# EVB-NORA-B2_SCHEM_0007_mikroE.net
KiCad netlist of a schematic drawn in Altium Designer
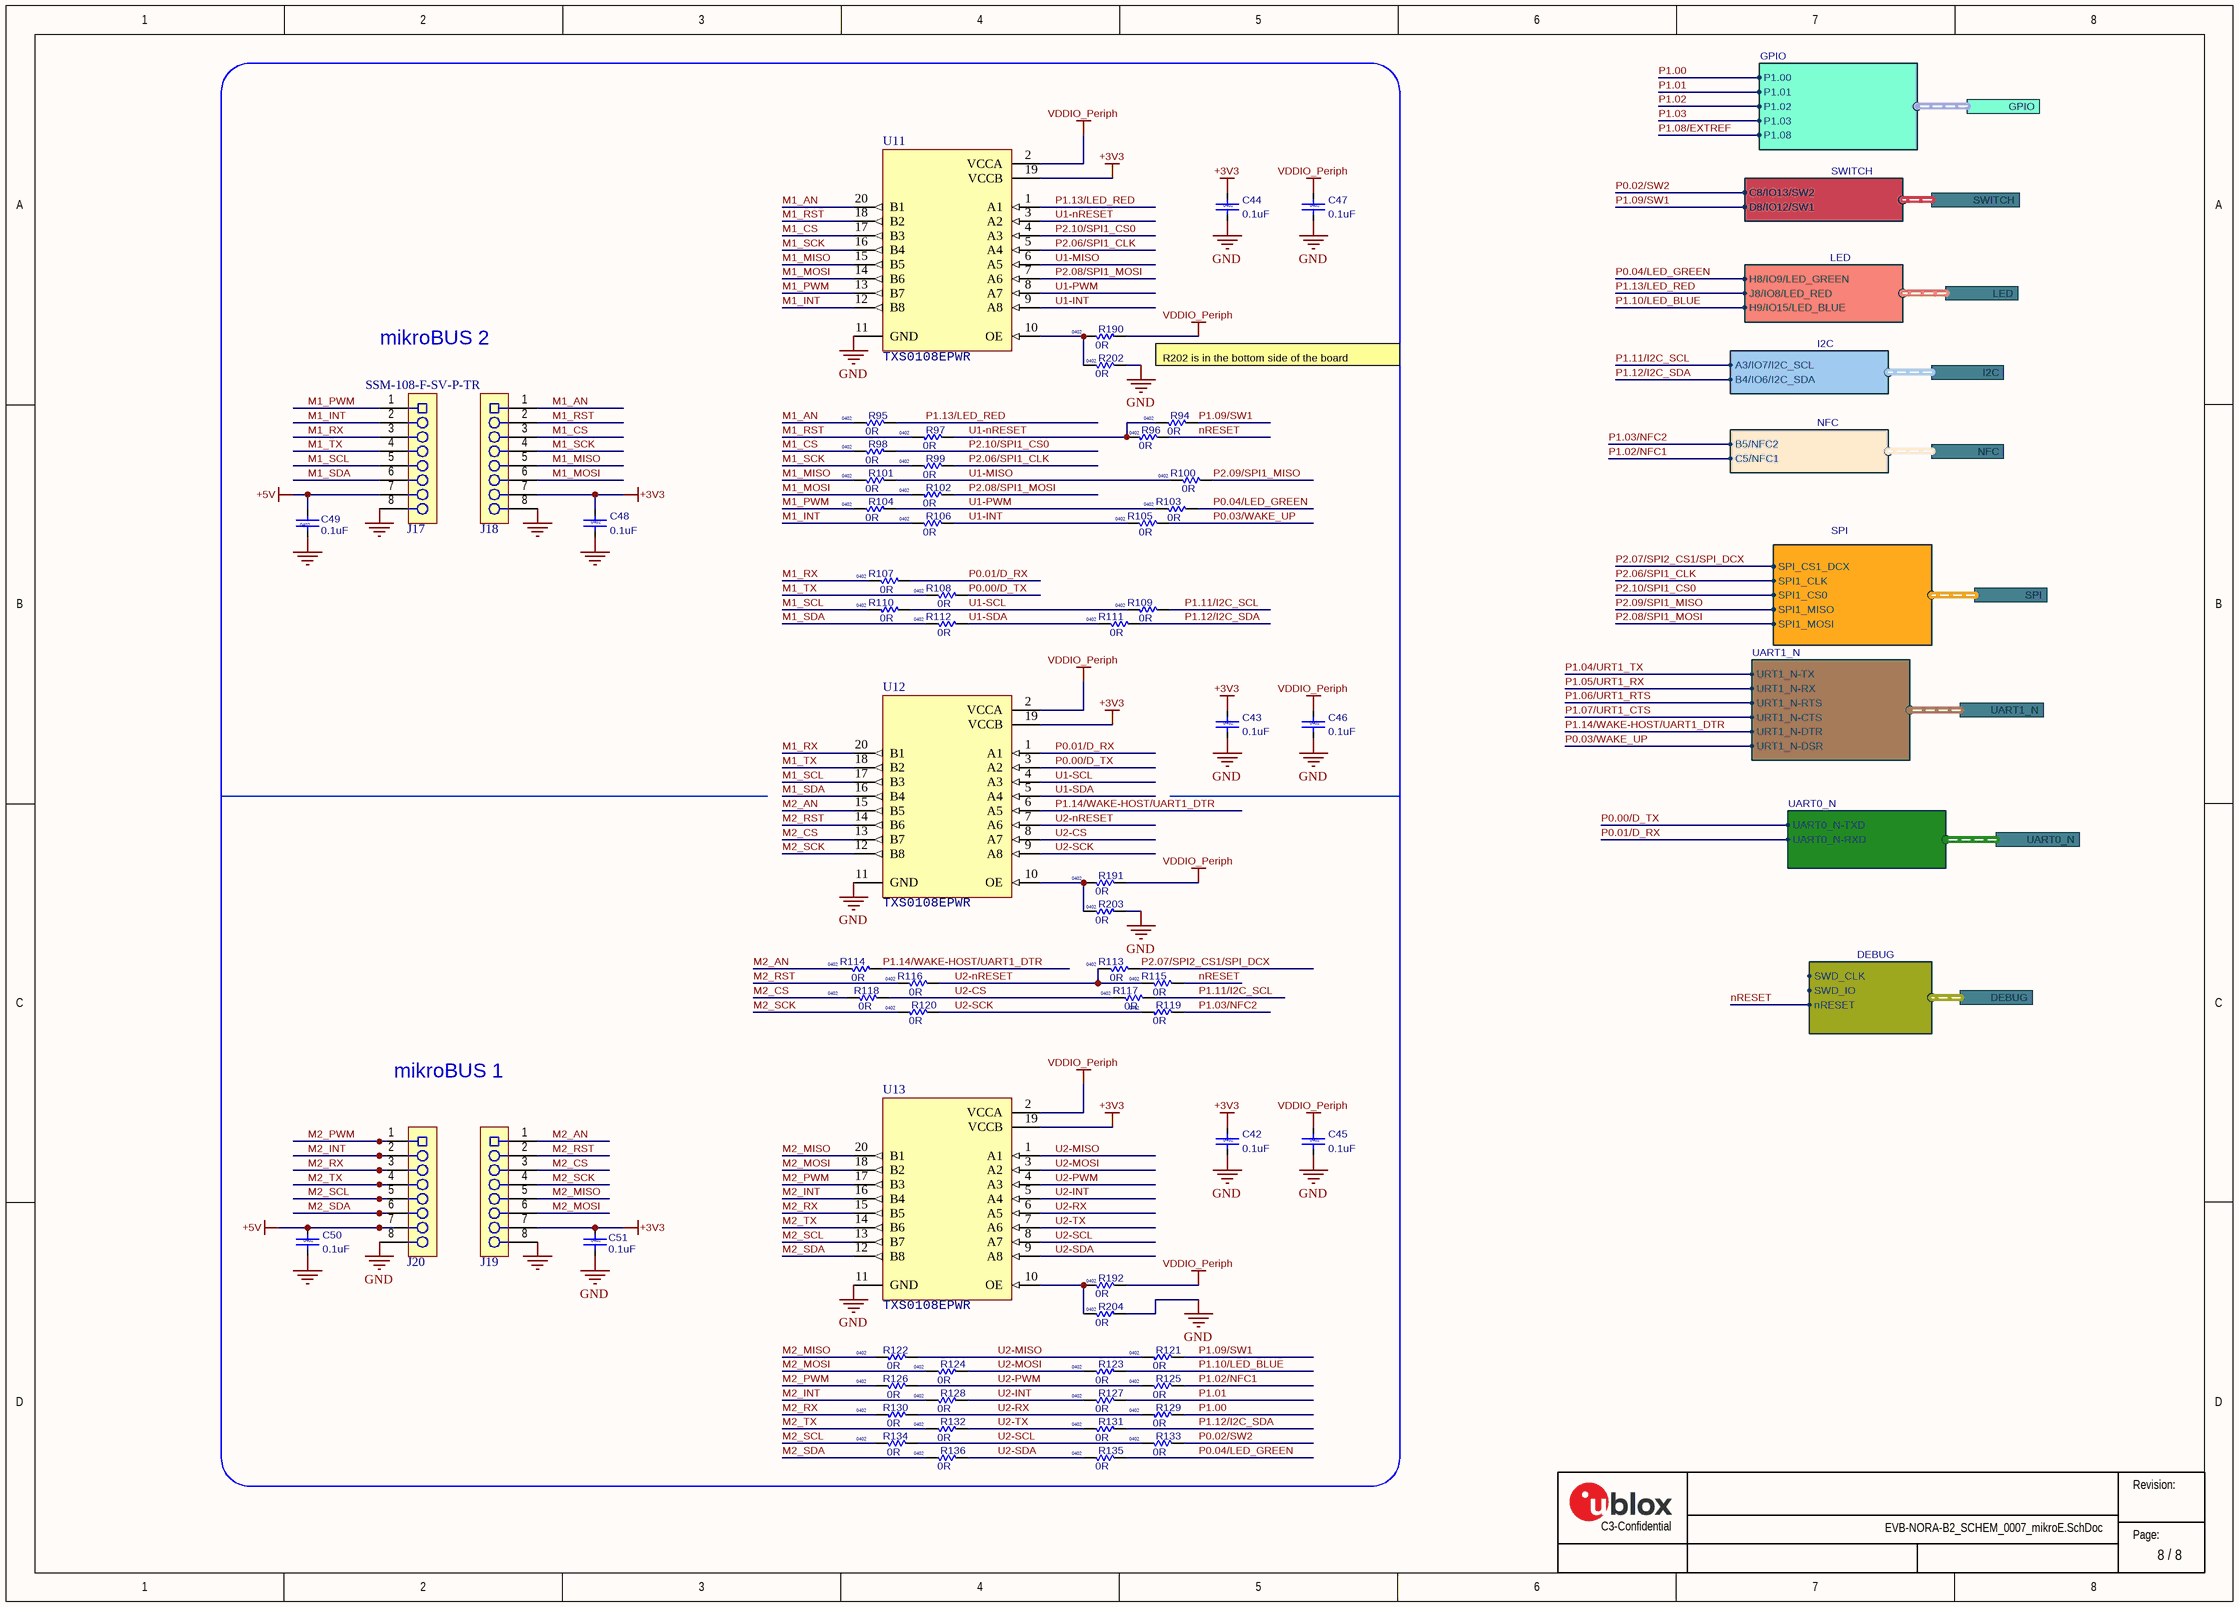
[diagram p0: EVB-NORA-B2_SCHEM_0007_mikroE.SchDoc]

(export (version "E")
  (design (tool "Eeschema 10.0.6"))
  (components
    (comp (ref "C42")
      (value "0.1uF")
      (footprint "Cap 0402 HD")
      (description "Cap, Ceramic 0.1uF 10V 10% X5R 0402")
      (fields
        (field (name "SIZE") "0402")
        (field (name "PART NUMBER") "120-00016")
        (field (name "MANUFACTURER") "Murata Electronics North America")
      )
      (libsource (lib "Arena_Parts_DB_Lib") (part "Cap Chip"))
    )
    (comp (ref "C43")
      (value "0.1uF")
      (footprint "Cap 0402 HD")
      (description "Cap, Ceramic 0.1uF 10V 10% X5R 0402")
      (fields
        (field (name "SIZE") "0402")
        (field (name "PART NUMBER") "120-00016")
        (field (name "MANUFACTURER") "Murata Electronics North America")
      )
      (libsource (lib "Arena_Parts_DB_Lib") (part "Cap Chip"))
    )
    (comp (ref "C44")
      (value "0.1uF")
      (footprint "Cap 0402 HD")
      (description "Cap, Ceramic 0.1uF 10V 10% X5R 0402")
      (fields
        (field (name "SIZE") "0402")
        (field (name "PART NUMBER") "120-00016")
        (field (name "MANUFACTURER") "Murata Electronics North America")
      )
      (libsource (lib "Arena_Parts_DB_Lib") (part "Cap Chip"))
    )
    (comp (ref "C45")
      (value "0.1uF")
      (footprint "Cap 0402 HD")
      (description "Cap, Ceramic 0.1uF 10V 10% X5R 0402")
      (fields
        (field (name "SIZE") "0402")
        (field (name "PART NUMBER") "120-00016")
        (field (name "MANUFACTURER") "Murata Electronics North America")
      )
      (libsource (lib "Arena_Parts_DB_Lib") (part "Cap Chip"))
    )
    (comp (ref "C46")
      (value "0.1uF")
      (footprint "Cap 0402 HD")
      (description "Cap, Ceramic 0.1uF 10V 10% X5R 0402")
      (fields
        (field (name "SIZE") "0402")
        (field (name "PART NUMBER") "120-00016")
        (field (name "MANUFACTURER") "Murata Electronics North America")
      )
      (libsource (lib "Arena_Parts_DB_Lib") (part "Cap Chip"))
    )
    (comp (ref "C47")
      (value "0.1uF")
      (footprint "Cap 0402 HD")
      (description "Cap, Ceramic 0.1uF 10V 10% X5R 0402")
      (fields
        (field (name "SIZE") "0402")
        (field (name "PART NUMBER") "120-00016")
        (field (name "MANUFACTURER") "Murata Electronics North America")
      )
      (libsource (lib "Arena_Parts_DB_Lib") (part "Cap Chip"))
    )
    (comp (ref "C48")
      (value "0.1uF")
      (footprint "Cap 0402 HD")
      (description "Cap, Ceramic 0.1uF 10V 10% X5R 0402")
      (fields
        (field (name "SIZE") "0402")
        (field (name "PART NUMBER") "120-00016")
        (field (name "MANUFACTURER") "Murata Electronics North America")
      )
      (libsource (lib "Arena_Parts_DB_Lib") (part "Cap Chip"))
    )
    (comp (ref "C49")
      (value "0.1uF")
      (footprint "Cap 0402 HD")
      (description "Cap, Ceramic 0.1uF 10V 10% X5R 0402")
      (fields
        (field (name "SIZE") "0402")
        (field (name "PART NUMBER") "120-00016")
        (field (name "MANUFACTURER") "Murata Electronics North America")
      )
      (libsource (lib "Arena_Parts_DB_Lib") (part "Cap Chip"))
    )
    (comp (ref "C50")
      (value "0.1uF")
      (footprint "Cap 0402 HD")
      (description "Cap, Ceramic 0.1uF 10V 10% X5R 0402")
      (fields
        (field (name "SIZE") "0402")
        (field (name "PART NUMBER") "120-00016")
        (field (name "MANUFACTURER") "Murata Electronics North America")
      )
      (libsource (lib "Arena_Parts_DB_Lib") (part "Cap Chip"))
    )
    (comp (ref "C51")
      (value "0.1uF")
      (footprint "Cap 0402 HD")
      (description "Cap, Ceramic 0.1uF 10V 10% X5R 0402")
      (fields
        (field (name "SIZE") "0402")
        (field (name "PART NUMBER") "120-00016")
        (field (name "MANUFACTURER") "Murata Electronics North America")
      )
      (libsource (lib "Arena_Parts_DB_Lib") (part "Cap Chip"))
    )
    (comp (ref "J17")
      (value "130-00102")
      (footprint "SKT-0.1P-SSM-108-L-SV")
      (description "Socket Strip 0.1\" 8 Pin 1Row SMD Black")
      (fields
        (field (name "MANUFACTURER PART NUMBER 1") "SSM-108-F-SV-P-TR")
        (field (name "VOLTAGE") "572VDC")
      )
      (libsource (lib "Arena_Parts_DB_Lib") (part "CON-8Pin_1Row"))
    )
    (comp (ref "J18")
      (value "130-00102")
      (footprint "SKT-0.1P-SSM-108-L-SV")
      (description "Socket Strip 0.1\" 8 Pin 1Row SMD Black")
      (fields (field (name "VOLTAGE") "572VDC"))
      (libsource (lib "") (part "CON-8Pin_1Row_1"))
    )
    (comp (ref "J19")
      (value "130-00102")
      (footprint "SKT-0.1P-SSM-108-L-SV")
      (description "Socket Strip 0.1\" 8 Pin 1Row SMD Black")
      (fields (field (name "VOLTAGE") "572VDC"))
      (libsource (lib "") (part "CON-8Pin_1Row_1"))
    )
    (comp (ref "J20")
      (value "130-00102")
      (footprint "SKT-0.1P-SSM-108-L-SV")
      (description "Socket Strip 0.1\" 8 Pin 1Row SMD Black")
      (fields (field (name "VOLTAGE") "572VDC"))
      (libsource (lib "Arena_Parts_DB_Lib") (part "CON-8Pin_1Row"))
    )
    (comp (ref "R94")
      (value "0R")
      (footprint "RES 0402 HD")
      (description "RES THICK FILM CHIP 0402 0R 0 100mW")
      (fields
        (field (name "SIZE") "0402")
        (field (name "PART NUMBER") "UBXH18-0003002")
        (field (name "TOLERANCE") "0")
        (field (name "EDITOR") "charlotte.biber")
        (field (name "RELEASED BY") "peter.mueller")
      )
      (libsource (lib "UBX_Parts_DB_Lib") (part "Res sm"))
    )
    (comp (ref "R95")
      (value "0R")
      (footprint "RES 0402 HD")
      (description "RES THICK FILM CHIP 0402 0R 0 100mW")
      (fields
        (field (name "SIZE") "0402")
        (field (name "PART NUMBER") "UBXH18-0003002")
        (field (name "TOLERANCE") "0")
        (field (name "EDITOR") "charlotte.biber")
        (field (name "RELEASED BY") "peter.mueller")
      )
      (libsource (lib "UBX_Parts_DB_Lib") (part "Res sm"))
    )
    (comp (ref "R96")
      (value "0R")
      (footprint "RES 0402 HD")
      (description "RES THICK FILM CHIP 0402 0R 0 100mW")
      (fields
        (field (name "SIZE") "0402")
        (field (name "PART NUMBER") "UBXH18-0003002")
        (field (name "TOLERANCE") "0")
        (field (name "EDITOR") "charlotte.biber")
        (field (name "RELEASED BY") "peter.mueller")
      )
      (libsource (lib "UBX_Parts_DB_Lib") (part "Res sm"))
    )
    (comp (ref "R97")
      (value "0R")
      (footprint "RES 0402 HD")
      (description "RES THICK FILM CHIP 0402 0R 0 100mW")
      (fields
        (field (name "SIZE") "0402")
        (field (name "PART NUMBER") "UBXH18-0003002")
        (field (name "TOLERANCE") "0")
        (field (name "EDITOR") "charlotte.biber")
        (field (name "RELEASED BY") "peter.mueller")
      )
      (libsource (lib "UBX_Parts_DB_Lib") (part "Res sm"))
    )
    (comp (ref "R98")
      (value "0R")
      (footprint "RES 0402 HD")
      (description "RES THICK FILM CHIP 0402 0R 0 100mW")
      (fields
        (field (name "SIZE") "0402")
        (field (name "PART NUMBER") "UBXH18-0003002")
        (field (name "TOLERANCE") "0")
        (field (name "EDITOR") "charlotte.biber")
        (field (name "RELEASED BY") "peter.mueller")
      )
      (libsource (lib "UBX_Parts_DB_Lib") (part "Res sm"))
    )
    (comp (ref "R99")
      (value "0R")
      (footprint "RES 0402 HD")
      (description "RES THICK FILM CHIP 0402 0R 0 100mW")
      (fields
        (field (name "SIZE") "0402")
        (field (name "PART NUMBER") "UBXH18-0003002")
        (field (name "TOLERANCE") "0")
        (field (name "EDITOR") "charlotte.biber")
        (field (name "RELEASED BY") "peter.mueller")
      )
      (libsource (lib "UBX_Parts_DB_Lib") (part "Res sm"))
    )
    (comp (ref "R100")
      (value "0R")
      (footprint "RES 0402 HD")
      (description "RES THICK FILM CHIP 0402 0R 0 100mW")
      (fields
        (field (name "SIZE") "0402")
        (field (name "PART NUMBER") "UBXH18-0003002")
        (field (name "TOLERANCE") "0")
        (field (name "EDITOR") "charlotte.biber")
        (field (name "RELEASED BY") "peter.mueller")
      )
      (libsource (lib "UBX_Parts_DB_Lib") (part "Res sm"))
    )
    (comp (ref "R101")
      (value "0R")
      (footprint "RES 0402 HD")
      (description "RES THICK FILM CHIP 0402 0R 0 100mW")
      (fields
        (field (name "SIZE") "0402")
        (field (name "PART NUMBER") "UBXH18-0003002")
        (field (name "TOLERANCE") "0")
        (field (name "EDITOR") "charlotte.biber")
        (field (name "RELEASED BY") "peter.mueller")
      )
      (libsource (lib "UBX_Parts_DB_Lib") (part "Res sm"))
    )
    (comp (ref "R102")
      (value "0R")
      (footprint "RES 0402 HD")
      (description "RES THICK FILM CHIP 0402 0R 0 100mW")
      (fields
        (field (name "SIZE") "0402")
        (field (name "PART NUMBER") "UBXH18-0003002")
        (field (name "TOLERANCE") "0")
        (field (name "EDITOR") "charlotte.biber")
        (field (name "RELEASED BY") "peter.mueller")
      )
      (libsource (lib "UBX_Parts_DB_Lib") (part "Res sm"))
    )
    (comp (ref "R103")
      (value "0R")
      (footprint "RES 0402 HD")
      (description "RES THICK FILM CHIP 0402 0R 0 100mW")
      (fields
        (field (name "SIZE") "0402")
        (field (name "PART NUMBER") "UBXH18-0003002")
        (field (name "TOLERANCE") "0")
        (field (name "EDITOR") "charlotte.biber")
        (field (name "RELEASED BY") "peter.mueller")
      )
      (libsource (lib "UBX_Parts_DB_Lib") (part "Res sm"))
    )
    (comp (ref "R104")
      (value "0R")
      (footprint "RES 0402 HD")
      (description "RES THICK FILM CHIP 0402 0R 0 100mW")
      (fields
        (field (name "SIZE") "0402")
        (field (name "PART NUMBER") "UBXH18-0003002")
        (field (name "TOLERANCE") "0")
        (field (name "EDITOR") "charlotte.biber")
        (field (name "RELEASED BY") "peter.mueller")
      )
      (libsource (lib "UBX_Parts_DB_Lib") (part "Res sm"))
    )
    (comp (ref "R105")
      (value "0R")
      (footprint "RES 0402 HD")
      (description "RES THICK FILM CHIP 0402 0R 0 100mW")
      (fields
        (field (name "SIZE") "0402")
        (field (name "PART NUMBER") "UBXH18-0003002")
        (field (name "TOLERANCE") "0")
        (field (name "EDITOR") "charlotte.biber")
        (field (name "RELEASED BY") "peter.mueller")
      )
      (libsource (lib "UBX_Parts_DB_Lib") (part "Res sm"))
    )
    (comp (ref "R106")
      (value "0R")
      (footprint "RES 0402 HD")
      (description "RES THICK FILM CHIP 0402 0R 0 100mW")
      (fields
        (field (name "SIZE") "0402")
        (field (name "PART NUMBER") "UBXH18-0003002")
        (field (name "TOLERANCE") "0")
        (field (name "EDITOR") "charlotte.biber")
        (field (name "RELEASED BY") "peter.mueller")
      )
      (libsource (lib "UBX_Parts_DB_Lib") (part "Res sm"))
    )
    (comp (ref "R107")
      (value "0R")
      (footprint "RES 0402 HD")
      (description "RES THICK FILM CHIP 0402 0R 0 100mW")
      (fields
        (field (name "SIZE") "0402")
        (field (name "PART NUMBER") "UBXH18-0003002")
        (field (name "TOLERANCE") "0")
        (field (name "EDITOR") "charlotte.biber")
        (field (name "RELEASED BY") "peter.mueller")
      )
      (libsource (lib "UBX_Parts_DB_Lib") (part "Res sm"))
    )
    (comp (ref "R108")
      (value "0R")
      (footprint "RES 0402 HD")
      (description "RES THICK FILM CHIP 0402 0R 0 100mW")
      (fields
        (field (name "SIZE") "0402")
        (field (name "PART NUMBER") "UBXH18-0003002")
        (field (name "TOLERANCE") "0")
        (field (name "EDITOR") "charlotte.biber")
        (field (name "RELEASED BY") "peter.mueller")
      )
      (libsource (lib "UBX_Parts_DB_Lib") (part "Res sm"))
    )
    (comp (ref "R109")
      (value "0R")
      (footprint "RES 0402 HD")
      (description "RES THICK FILM CHIP 0402 0R 0 100mW")
      (fields
        (field (name "SIZE") "0402")
        (field (name "PART NUMBER") "UBXH18-0003002")
        (field (name "TOLERANCE") "0")
        (field (name "EDITOR") "charlotte.biber")
        (field (name "RELEASED BY") "peter.mueller")
      )
      (libsource (lib "UBX_Parts_DB_Lib") (part "Res sm"))
    )
    (comp (ref "R110")
      (value "0R")
      (footprint "RES 0402 HD")
      (description "RES THICK FILM CHIP 0402 0R 0 100mW")
      (fields
        (field (name "SIZE") "0402")
        (field (name "PART NUMBER") "UBXH18-0003002")
        (field (name "TOLERANCE") "0")
        (field (name "EDITOR") "charlotte.biber")
        (field (name "RELEASED BY") "peter.mueller")
      )
      (libsource (lib "UBX_Parts_DB_Lib") (part "Res sm"))
    )
    (comp (ref "R111")
      (value "0R")
      (footprint "RES 0402 HD")
      (description "RES THICK FILM CHIP 0402 0R 0 100mW")
      (fields
        (field (name "SIZE") "0402")
        (field (name "PART NUMBER") "UBXH18-0003002")
        (field (name "TOLERANCE") "0")
        (field (name "EDITOR") "charlotte.biber")
        (field (name "RELEASED BY") "peter.mueller")
      )
      (libsource (lib "UBX_Parts_DB_Lib") (part "Res sm"))
    )
    (comp (ref "R112")
      (value "0R")
      (footprint "RES 0402 HD")
      (description "RES THICK FILM CHIP 0402 0R 0 100mW")
      (fields
        (field (name "SIZE") "0402")
        (field (name "PART NUMBER") "UBXH18-0003002")
        (field (name "TOLERANCE") "0")
        (field (name "EDITOR") "charlotte.biber")
        (field (name "RELEASED BY") "peter.mueller")
      )
      (libsource (lib "UBX_Parts_DB_Lib") (part "Res sm"))
    )
    (comp (ref "R113")
      (value "0R")
      (footprint "RES 0402 HD")
      (description "RES THICK FILM CHIP 0402 0R 0 100mW")
      (fields
        (field (name "SIZE") "0402")
        (field (name "PART NUMBER") "UBXH18-0003002")
        (field (name "TOLERANCE") "0")
        (field (name "EDITOR") "charlotte.biber")
        (field (name "RELEASED BY") "peter.mueller")
      )
      (libsource (lib "UBX_Parts_DB_Lib") (part "Res sm"))
    )
    (comp (ref "R114")
      (value "0R")
      (footprint "RES 0402 HD")
      (description "RES THICK FILM CHIP 0402 0R 0 100mW")
      (fields
        (field (name "SIZE") "0402")
        (field (name "PART NUMBER") "UBXH18-0003002")
        (field (name "TOLERANCE") "0")
        (field (name "EDITOR") "charlotte.biber")
        (field (name "RELEASED BY") "peter.mueller")
      )
      (libsource (lib "UBX_Parts_DB_Lib") (part "Res sm"))
    )
    (comp (ref "R115")
      (value "0R")
      (footprint "RES 0402 HD")
      (description "RES THICK FILM CHIP 0402 0R 0 100mW")
      (fields
        (field (name "SIZE") "0402")
        (field (name "PART NUMBER") "UBXH18-0003002")
        (field (name "TOLERANCE") "0")
        (field (name "EDITOR") "charlotte.biber")
        (field (name "RELEASED BY") "peter.mueller")
      )
      (libsource (lib "UBX_Parts_DB_Lib") (part "Res sm"))
    )
    (comp (ref "R116")
      (value "0R")
      (footprint "RES 0402 HD")
      (description "RES THICK FILM CHIP 0402 0R 0 100mW")
      (fields
        (field (name "SIZE") "0402")
        (field (name "PART NUMBER") "UBXH18-0003002")
        (field (name "TOLERANCE") "0")
        (field (name "EDITOR") "charlotte.biber")
        (field (name "RELEASED BY") "peter.mueller")
      )
      (libsource (lib "UBX_Parts_DB_Lib") (part "Res sm"))
    )
    (comp (ref "R117")
      (value "0R")
      (footprint "RES 0402 HD")
      (description "RES THICK FILM CHIP 0402 0R 0 100mW")
      (fields
        (field (name "SIZE") "0402")
        (field (name "PART NUMBER") "UBXH18-0003002")
        (field (name "TOLERANCE") "0")
        (field (name "EDITOR") "charlotte.biber")
        (field (name "RELEASED BY") "peter.mueller")
      )
      (libsource (lib "UBX_Parts_DB_Lib") (part "Res sm"))
    )
    (comp (ref "R118")
      (value "0R")
      (footprint "RES 0402 HD")
      (description "RES THICK FILM CHIP 0402 0R 0 100mW")
      (fields
        (field (name "SIZE") "0402")
        (field (name "PART NUMBER") "UBXH18-0003002")
        (field (name "TOLERANCE") "0")
        (field (name "EDITOR") "charlotte.biber")
        (field (name "RELEASED BY") "peter.mueller")
      )
      (libsource (lib "UBX_Parts_DB_Lib") (part "Res sm"))
    )
    (comp (ref "R119")
      (value "0R")
      (footprint "RES 0402 HD")
      (description "RES THICK FILM CHIP 0402 0R 0 100mW")
      (fields
        (field (name "SIZE") "0402")
        (field (name "PART NUMBER") "UBXH18-0003002")
        (field (name "TOLERANCE") "0")
        (field (name "EDITOR") "charlotte.biber")
        (field (name "RELEASED BY") "peter.mueller")
      )
      (libsource (lib "UBX_Parts_DB_Lib") (part "Res sm"))
    )
    (comp (ref "R120")
      (value "0R")
      (footprint "RES 0402 HD")
      (description "RES THICK FILM CHIP 0402 0R 0 100mW")
      (fields
        (field (name "SIZE") "0402")
        (field (name "PART NUMBER") "UBXH18-0003002")
        (field (name "TOLERANCE") "0")
        (field (name "EDITOR") "charlotte.biber")
        (field (name "RELEASED BY") "peter.mueller")
      )
      (libsource (lib "UBX_Parts_DB_Lib") (part "Res sm"))
    )
    (comp (ref "R121")
      (value "0R")
      (footprint "RES 0402 HD")
      (description "RES THICK FILM CHIP 0402 0R 0 100mW")
      (fields
        (field (name "SIZE") "0402")
        (field (name "PART NUMBER") "UBXH18-0003002")
        (field (name "TOLERANCE") "0")
        (field (name "EDITOR") "charlotte.biber")
        (field (name "RELEASED BY") "peter.mueller")
      )
      (libsource (lib "UBX_Parts_DB_Lib") (part "Res sm"))
    )
    (comp (ref "R122")
      (value "0R")
      (footprint "RES 0402 HD")
      (description "RES THICK FILM CHIP 0402 0R 0 100mW")
      (fields
        (field (name "SIZE") "0402")
        (field (name "PART NUMBER") "UBXH18-0003002")
        (field (name "TOLERANCE") "0")
        (field (name "EDITOR") "charlotte.biber")
        (field (name "RELEASED BY") "peter.mueller")
      )
      (libsource (lib "UBX_Parts_DB_Lib") (part "Res sm"))
    )
    (comp (ref "R123")
      (value "0R")
      (footprint "RES 0402 HD")
      (description "RES THICK FILM CHIP 0402 0R 0 100mW")
      (fields
        (field (name "SIZE") "0402")
        (field (name "PART NUMBER") "UBXH18-0003002")
        (field (name "TOLERANCE") "0")
        (field (name "EDITOR") "charlotte.biber")
        (field (name "RELEASED BY") "peter.mueller")
      )
      (libsource (lib "UBX_Parts_DB_Lib") (part "Res sm"))
    )
    (comp (ref "R124")
      (value "0R")
      (footprint "RES 0402 HD")
      (description "RES THICK FILM CHIP 0402 0R 0 100mW")
      (fields
        (field (name "SIZE") "0402")
        (field (name "PART NUMBER") "UBXH18-0003002")
        (field (name "TOLERANCE") "0")
        (field (name "EDITOR") "charlotte.biber")
        (field (name "RELEASED BY") "peter.mueller")
      )
      (libsource (lib "UBX_Parts_DB_Lib") (part "Res sm"))
    )
    (comp (ref "R125")
      (value "0R")
      (footprint "RES 0402 HD")
      (description "RES THICK FILM CHIP 0402 0R 0 100mW")
      (fields
        (field (name "SIZE") "0402")
        (field (name "PART NUMBER") "UBXH18-0003002")
        (field (name "TOLERANCE") "0")
        (field (name "EDITOR") "charlotte.biber")
        (field (name "RELEASED BY") "peter.mueller")
      )
      (libsource (lib "UBX_Parts_DB_Lib") (part "Res sm"))
    )
    (comp (ref "R126")
      (value "0R")
      (footprint "RES 0402 HD")
      (description "RES THICK FILM CHIP 0402 0R 0 100mW")
      (fields
        (field (name "SIZE") "0402")
        (field (name "PART NUMBER") "UBXH18-0003002")
        (field (name "TOLERANCE") "0")
        (field (name "EDITOR") "charlotte.biber")
        (field (name "RELEASED BY") "peter.mueller")
      )
      (libsource (lib "UBX_Parts_DB_Lib") (part "Res sm"))
    )
    (comp (ref "R127")
      (value "0R")
      (footprint "RES 0402 HD")
      (description "RES THICK FILM CHIP 0402 0R 0 100mW")
      (fields
        (field (name "SIZE") "0402")
        (field (name "PART NUMBER") "UBXH18-0003002")
        (field (name "TOLERANCE") "0")
        (field (name "EDITOR") "charlotte.biber")
        (field (name "RELEASED BY") "peter.mueller")
      )
      (libsource (lib "UBX_Parts_DB_Lib") (part "Res sm"))
    )
    (comp (ref "R128")
      (value "0R")
      (footprint "RES 0402 HD")
      (description "RES THICK FILM CHIP 0402 0R 0 100mW")
      (fields
        (field (name "SIZE") "0402")
        (field (name "PART NUMBER") "UBXH18-0003002")
        (field (name "TOLERANCE") "0")
        (field (name "EDITOR") "charlotte.biber")
        (field (name "RELEASED BY") "peter.mueller")
      )
      (libsource (lib "UBX_Parts_DB_Lib") (part "Res sm"))
    )
    (comp (ref "R129")
      (value "0R")
      (footprint "RES 0402 HD")
      (description "RES THICK FILM CHIP 0402 0R 0 100mW")
      (fields
        (field (name "SIZE") "0402")
        (field (name "PART NUMBER") "UBXH18-0003002")
        (field (name "TOLERANCE") "0")
        (field (name "EDITOR") "charlotte.biber")
        (field (name "RELEASED BY") "peter.mueller")
      )
      (libsource (lib "UBX_Parts_DB_Lib") (part "Res sm"))
    )
    (comp (ref "R130")
      (value "0R")
      (footprint "RES 0402 HD")
      (description "RES THICK FILM CHIP 0402 0R 0 100mW")
      (fields
        (field (name "SIZE") "0402")
        (field (name "PART NUMBER") "UBXH18-0003002")
        (field (name "TOLERANCE") "0")
        (field (name "EDITOR") "charlotte.biber")
        (field (name "RELEASED BY") "peter.mueller")
      )
      (libsource (lib "UBX_Parts_DB_Lib") (part "Res sm"))
    )
    (comp (ref "R131")
      (value "0R")
      (footprint "RES 0402 HD")
      (description "RES THICK FILM CHIP 0402 0R 0 100mW")
      (fields
        (field (name "SIZE") "0402")
        (field (name "PART NUMBER") "UBXH18-0003002")
        (field (name "TOLERANCE") "0")
        (field (name "EDITOR") "charlotte.biber")
        (field (name "RELEASED BY") "peter.mueller")
      )
      (libsource (lib "UBX_Parts_DB_Lib") (part "Res sm"))
    )
    (comp (ref "R132")
      (value "0R")
      (footprint "RES 0402 HD")
      (description "RES THICK FILM CHIP 0402 0R 0 100mW")
      (fields
        (field (name "SIZE") "0402")
        (field (name "PART NUMBER") "UBXH18-0003002")
        (field (name "TOLERANCE") "0")
        (field (name "EDITOR") "charlotte.biber")
        (field (name "RELEASED BY") "peter.mueller")
      )
      (libsource (lib "UBX_Parts_DB_Lib") (part "Res sm"))
    )
    (comp (ref "R133")
      (value "0R")
      (footprint "RES 0402 HD")
      (description "RES THICK FILM CHIP 0402 0R 0 100mW")
      (fields
        (field (name "SIZE") "0402")
        (field (name "PART NUMBER") "UBXH18-0003002")
        (field (name "TOLERANCE") "0")
        (field (name "EDITOR") "charlotte.biber")
        (field (name "RELEASED BY") "peter.mueller")
      )
      (libsource (lib "UBX_Parts_DB_Lib") (part "Res sm"))
    )
    (comp (ref "R134")
      (value "0R")
      (footprint "RES 0402 HD")
      (description "RES THICK FILM CHIP 0402 0R 0 100mW")
      (fields
        (field (name "SIZE") "0402")
        (field (name "PART NUMBER") "UBXH18-0003002")
        (field (name "TOLERANCE") "0")
        (field (name "EDITOR") "charlotte.biber")
        (field (name "RELEASED BY") "peter.mueller")
      )
      (libsource (lib "UBX_Parts_DB_Lib") (part "Res sm"))
    )
    (comp (ref "R135")
      (value "0R")
      (footprint "RES 0402 HD")
      (description "RES THICK FILM CHIP 0402 0R 0 100mW")
      (fields
        (field (name "SIZE") "0402")
        (field (name "PART NUMBER") "UBXH18-0003002")
        (field (name "TOLERANCE") "0")
        (field (name "EDITOR") "charlotte.biber")
        (field (name "RELEASED BY") "peter.mueller")
      )
      (libsource (lib "UBX_Parts_DB_Lib") (part "Res sm"))
    )
    (comp (ref "R136")
      (value "0R")
      (footprint "RES 0402 HD")
      (description "RES THICK FILM CHIP 0402 0R 0 100mW")
      (fields
        (field (name "SIZE") "0402")
        (field (name "PART NUMBER") "UBXH18-0003002")
        (field (name "TOLERANCE") "0")
        (field (name "EDITOR") "charlotte.biber")
        (field (name "RELEASED BY") "peter.mueller")
      )
      (libsource (lib "UBX_Parts_DB_Lib") (part "Res sm"))
    )
    (comp (ref "R190")
      (value "0R")
      (footprint "RES 0402 HD")
      (description "RES THICK FILM CHIP 0402 0R 0 100mW")
      (fields
        (field (name "SIZE") "0402")
        (field (name "PART NUMBER") "UBXH18-0003002")
        (field (name "TOLERANCE") "0")
        (field (name "EDITOR") "charlotte.biber")
        (field (name "RELEASED BY") "peter.mueller")
      )
      (libsource (lib "UBX_Parts_DB_Lib") (part "Res sm"))
    )
    (comp (ref "R191")
      (value "0R")
      (footprint "RES 0402 HD")
      (description "RES THICK FILM CHIP 0402 0R 0 100mW")
      (fields
        (field (name "SIZE") "0402")
        (field (name "PART NUMBER") "UBXH18-0003002")
        (field (name "TOLERANCE") "0")
        (field (name "EDITOR") "charlotte.biber")
        (field (name "RELEASED BY") "peter.mueller")
      )
      (libsource (lib "UBX_Parts_DB_Lib") (part "Res sm"))
    )
    (comp (ref "R192")
      (value "0R")
      (footprint "RES 0402 HD")
      (description "RES THICK FILM CHIP 0402 0R 0 100mW")
      (fields
        (field (name "SIZE") "0402")
        (field (name "PART NUMBER") "UBXH18-0003002")
        (field (name "TOLERANCE") "0")
        (field (name "EDITOR") "charlotte.biber")
        (field (name "RELEASED BY") "peter.mueller")
      )
      (libsource (lib "UBX_Parts_DB_Lib") (part "Res sm"))
    )
    (comp (ref "R202")
      (value "0R")
      (footprint "RES 0402 HD")
      (description "RES THICK FILM CHIP 0402 0R 0 100mW")
      (fields
        (field (name "SIZE") "0402")
        (field (name "PART NUMBER") "UBXH18-0003002")
        (field (name "TOLERANCE") "0")
        (field (name "EDITOR") "charlotte.biber")
        (field (name "RELEASED BY") "peter.mueller")
      )
      (libsource (lib "UBX_Parts_DB_Lib") (part "Res sm"))
    )
    (comp (ref "R203")
      (value "0R")
      (footprint "RES 0402 HD")
      (description "RES THICK FILM CHIP 0402 0R 0 100mW")
      (fields
        (field (name "SIZE") "0402")
        (field (name "PART NUMBER") "UBXH18-0003002")
        (field (name "TOLERANCE") "0")
        (field (name "EDITOR") "charlotte.biber")
        (field (name "RELEASED BY") "peter.mueller")
      )
      (libsource (lib "UBX_Parts_DB_Lib") (part "Res sm"))
    )
    (comp (ref "R204")
      (value "0R")
      (footprint "RES 0402 HD")
      (description "RES THICK FILM CHIP 0402 0R 0 100mW")
      (fields
        (field (name "SIZE") "0402")
        (field (name "PART NUMBER") "UBXH18-0003002")
        (field (name "TOLERANCE") "0")
        (field (name "EDITOR") "charlotte.biber")
        (field (name "RELEASED BY") "peter.mueller")
      )
      (libsource (lib "UBX_Parts_DB_Lib") (part "Res sm"))
    )
    (comp (ref "U11")
      (value "UBXH10-0000036")
      (footprint "TSOP0.65P6.40X1.20-20Pin")
      (description "TXS0108 8-BIT BIDIRECTIONAL VOLTAGE-LEVEL TRANSLATOR")
      (fields
        (field (name "MANUFACTURER P/N") "TXS0108EPWR")
        (field (name "MANUFACTURER") "Texas Instruments")
        (field (name "EDITOR") "roland.rust")
        (field (name "RELEASED BY") "adam.johansson")
      )
      (libsource (lib "UBX_Parts_DB_Lib") (part "TXS0108EPWR"))
    )
    (comp (ref "U12")
      (value "UBXH10-0000036")
      (footprint "TSOP0.65P6.40X1.20-20Pin")
      (description "TXS0108 8-BIT BIDIRECTIONAL VOLTAGE-LEVEL TRANSLATOR")
      (fields
        (field (name "MANUFACTURER P/N") "TXS0108EPWR")
        (field (name "MANUFACTURER") "Texas Instruments")
        (field (name "EDITOR") "roland.rust")
        (field (name "RELEASED BY") "adam.johansson")
      )
      (libsource (lib "UBX_Parts_DB_Lib") (part "TXS0108EPWR"))
    )
    (comp (ref "U13")
      (value "UBXH10-0000036")
      (footprint "TSOP0.65P6.40X1.20-20Pin")
      (description "TXS0108 8-BIT BIDIRECTIONAL VOLTAGE-LEVEL TRANSLATOR")
      (fields
        (field (name "MANUFACTURER P/N") "TXS0108EPWR")
        (field (name "MANUFACTURER") "Texas Instruments")
        (field (name "EDITOR") "roland.rust")
        (field (name "RELEASED BY") "adam.johansson")
      )
      (libsource (lib "UBX_Parts_DB_Lib") (part "TXS0108EPWR"))
    )
  )
  (nets
    (net (code "10") (name "+3V3") (class "Default")
      (node (ref "C42") (pin "1") (pinfunction "1_1") (pintype "passive"))
      (node (ref "C43") (pin "1") (pinfunction "1_1") (pintype "passive"))
      (node (ref "C44") (pin "1") (pinfunction "1_1") (pintype "passive"))
      (node (ref "C48") (pin "1") (pinfunction "1_1") (pintype "passive"))
      (node (ref "C51") (pin "1") (pinfunction "1_1") (pintype "passive"))
      (node (ref "J18") (pin "7") (pintype "passive"))
      (node (ref "J19") (pin "7") (pintype "passive"))
      (node (ref "U11") (pin "19") (pinfunction "VCCB_19") (pintype "power_in"))
      (node (ref "U12") (pin "19") (pinfunction "VCCB_19") (pintype "power_in"))
      (node (ref "U13") (pin "19") (pinfunction "VCCB_19") (pintype "power_in"))
    )
    (net (code "11") (name "+5V") (class "Default")
      (node (ref "C49") (pin "2") (pinfunction "2_2") (pintype "passive"))
      (node (ref "C50") (pin "1") (pinfunction "1_1") (pintype "passive"))
      (node (ref "J17") (pin "7") (pintype "passive"))
      (node (ref "J20") (pin "7") (pintype "passive"))
    )
    (net (code "12") (name "/M1_AN") (class "Default")
      (node (ref "J18") (pin "1") (pintype "passive"))
      (node (ref "R95") (pin "1") (pinfunction "1_1") (pintype "passive"))
      (node (ref "U11") (pin "20") (pinfunction "B1_20") (pintype "output"))
    )
    (net (code "13") (name "/M1_CS") (class "Default")
      (node (ref "J18") (pin "3") (pintype "passive"))
      (node (ref "R98") (pin "1") (pinfunction "1_1") (pintype "passive"))
      (node (ref "U11") (pin "17") (pinfunction "B3_17") (pintype "output"))
    )
    (net (code "14") (name "/M1_INT") (class "Default")
      (node (ref "J17") (pin "2") (pintype "passive"))
      (node (ref "R106") (pin "1") (pinfunction "1_1") (pintype "passive"))
      (node (ref "U11") (pin "12") (pinfunction "B8_12") (pintype "output"))
    )
    (net (code "15") (name "/M1_MISO") (class "Default")
      (node (ref "J18") (pin "5") (pintype "passive"))
      (node (ref "R101") (pin "1") (pinfunction "1_1") (pintype "passive"))
      (node (ref "U11") (pin "15") (pinfunction "B5_15") (pintype "output"))
    )
    (net (code "16") (name "/M1_MOSI") (class "Default")
      (node (ref "J18") (pin "6") (pintype "passive"))
      (node (ref "R102") (pin "1") (pinfunction "1_1") (pintype "passive"))
      (node (ref "U11") (pin "14") (pinfunction "B6_14") (pintype "output"))
    )
    (net (code "17") (name "/M1_PWM") (class "Default")
      (node (ref "J17") (pin "1") (pintype "passive"))
      (node (ref "R104") (pin "1") (pinfunction "1_1") (pintype "passive"))
      (node (ref "U11") (pin "13") (pinfunction "B7_13") (pintype "output"))
    )
    (net (code "18") (name "/M1_RST") (class "Default")
      (node (ref "J18") (pin "2") (pintype "passive"))
      (node (ref "R97") (pin "1") (pinfunction "1_1") (pintype "passive"))
      (node (ref "U11") (pin "18") (pinfunction "B2_18") (pintype "output"))
    )
    (net (code "19") (name "/M1_RX") (class "Default")
      (node (ref "J17") (pin "3") (pintype "passive"))
      (node (ref "R107") (pin "1") (pinfunction "1_1") (pintype "passive"))
      (node (ref "U12") (pin "20") (pinfunction "B1_20") (pintype "output"))
    )
    (net (code "20") (name "/M1_SCK") (class "Default")
      (node (ref "J18") (pin "4") (pintype "passive"))
      (node (ref "R99") (pin "1") (pinfunction "1_1") (pintype "passive"))
      (node (ref "U11") (pin "16") (pinfunction "B4_16") (pintype "output"))
    )
    (net (code "21") (name "/M1_SCL") (class "Default")
      (node (ref "J17") (pin "5") (pintype "passive"))
      (node (ref "R110") (pin "1") (pinfunction "1_1") (pintype "passive"))
      (node (ref "U12") (pin "17") (pinfunction "B3_17") (pintype "output"))
    )
    (net (code "22") (name "/M1_SDA") (class "Default")
      (node (ref "J17") (pin "6") (pintype "passive"))
      (node (ref "R112") (pin "1") (pinfunction "1_1") (pintype "passive"))
      (node (ref "U12") (pin "16") (pinfunction "B4_16") (pintype "output"))
    )
    (net (code "23") (name "/M1_TX") (class "Default")
      (node (ref "J17") (pin "4") (pintype "passive"))
      (node (ref "R108") (pin "1") (pinfunction "1_1") (pintype "passive"))
      (node (ref "U12") (pin "18") (pinfunction "B2_18") (pintype "output"))
    )
    (net (code "24") (name "/M2_AN") (class "Default")
      (node (ref "J19") (pin "1") (pintype "passive"))
      (node (ref "R114") (pin "1") (pinfunction "1_1") (pintype "passive"))
      (node (ref "U12") (pin "15") (pinfunction "B5_15") (pintype "output"))
    )
    (net (code "25") (name "/M2_CS") (class "Default")
      (node (ref "J19") (pin "3") (pintype "passive"))
      (node (ref "R118") (pin "1") (pinfunction "1_1") (pintype "passive"))
      (node (ref "U12") (pin "13") (pinfunction "B7_13") (pintype "output"))
    )
    (net (code "26") (name "/M2_INT") (class "Default")
      (node (ref "J20") (pin "2") (pintype "passive"))
      (node (ref "R128") (pin "1") (pinfunction "1_1") (pintype "passive"))
      (node (ref "U13") (pin "16") (pinfunction "B4_16") (pintype "output"))
    )
    (net (code "27") (name "/M2_MISO") (class "Default")
      (node (ref "J19") (pin "5") (pintype "passive"))
      (node (ref "R122") (pin "1") (pinfunction "1_1") (pintype "passive"))
      (node (ref "U13") (pin "20") (pinfunction "B1_20") (pintype "output"))
    )
    (net (code "28") (name "/M2_MOSI") (class "Default")
      (node (ref "J19") (pin "6") (pintype "passive"))
      (node (ref "R124") (pin "1") (pinfunction "1_1") (pintype "passive"))
      (node (ref "U13") (pin "18") (pinfunction "B2_18") (pintype "output"))
    )
    (net (code "29") (name "/M2_PWM") (class "Default")
      (node (ref "J20") (pin "1") (pintype "passive"))
      (node (ref "R126") (pin "1") (pinfunction "1_1") (pintype "passive"))
      (node (ref "U13") (pin "17") (pinfunction "B3_17") (pintype "output"))
    )
    (net (code "30") (name "/M2_RST") (class "Default")
      (node (ref "J19") (pin "2") (pintype "passive"))
      (node (ref "R116") (pin "1") (pinfunction "1_1") (pintype "passive"))
      (node (ref "U12") (pin "14") (pinfunction "B6_14") (pintype "output"))
    )
    (net (code "31") (name "/M2_RX") (class "Default")
      (node (ref "J20") (pin "3") (pintype "passive"))
      (node (ref "R130") (pin "1") (pinfunction "1_1") (pintype "passive"))
      (node (ref "U13") (pin "15") (pinfunction "B5_15") (pintype "output"))
    )
    (net (code "32") (name "/M2_SCK") (class "Default")
      (node (ref "J19") (pin "4") (pintype "passive"))
      (node (ref "R120") (pin "1") (pinfunction "1_1") (pintype "passive"))
      (node (ref "U12") (pin "12") (pinfunction "B8_12") (pintype "output"))
    )
    (net (code "33") (name "/M2_SCL") (class "Default")
      (node (ref "J20") (pin "5") (pintype "passive"))
      (node (ref "R134") (pin "1") (pinfunction "1_1") (pintype "passive"))
      (node (ref "U13") (pin "13") (pinfunction "B7_13") (pintype "output"))
    )
    (net (code "34") (name "/M2_SDA") (class "Default")
      (node (ref "J20") (pin "6") (pintype "passive"))
      (node (ref "R136") (pin "1") (pinfunction "1_1") (pintype "passive"))
      (node (ref "U13") (pin "12") (pinfunction "B8_12") (pintype "output"))
    )
    (net (code "35") (name "/M2_TX") (class "Default")
      (node (ref "J20") (pin "4") (pintype "passive"))
      (node (ref "R132") (pin "1") (pinfunction "1_1") (pintype "passive"))
      (node (ref "U13") (pin "14") (pinfunction "B6_14") (pintype "output"))
    )
    (net (code "36") (name "/P0.00{slash}D_TX") (class "Default")
      (node (ref "R108") (pin "2") (pinfunction "2_2") (pintype "passive"))
      (node (ref "U12") (pin "3") (pinfunction "A2_3") (pintype "input"))
    )
    (net (code "37") (name "/P0.01{slash}D_RX") (class "Default")
      (node (ref "R107") (pin "2") (pinfunction "2_2") (pintype "passive"))
      (node (ref "U12") (pin "1") (pinfunction "A1_1") (pintype "input"))
    )
    (net (code "38") (name "/P0.02{slash}SW2") (class "Default")
      (node (ref "R133") (pin "2") (pinfunction "2_2") (pintype "passive"))
    )
    (net (code "39") (name "/P0.03{slash}WAKE_UP") (class "Default")
      (node (ref "R105") (pin "2") (pinfunction "2_2") (pintype "passive"))
    )
    (net (code "40") (name "/P0.04{slash}LED_GREEN") (class "Default")
      (node (ref "R103") (pin "2") (pinfunction "2_2") (pintype "passive"))
      (node (ref "R135") (pin "2") (pinfunction "2_2") (pintype "passive"))
    )
    (net (code "41") (name "/P1.00") (class "Default")
      (node (ref "R129") (pin "2") (pinfunction "2_2") (pintype "passive"))
    )
    (net (code "42") (name "/P1.01") (class "Default")
      (node (ref "R127") (pin "2") (pinfunction "2_2") (pintype "passive"))
    )
    (net (code "44") (name "/P1.02{slash}NFC1") (class "Default")
      (node (ref "R125") (pin "2") (pinfunction "2_2") (pintype "passive"))
    )
    (net (code "46") (name "/P1.03{slash}NFC2") (class "Default")
      (node (ref "R119") (pin "2") (pinfunction "2_2") (pintype "passive"))
    )
    (net (code "52") (name "/P1.09{slash}SW1") (class "Default")
      (node (ref "R121") (pin "2") (pinfunction "2_2") (pintype "passive"))
      (node (ref "R94") (pin "2") (pinfunction "2_2") (pintype "passive"))
    )
    (net (code "53") (name "/P1.10{slash}LED_BLUE") (class "Default")
      (node (ref "R123") (pin "2") (pinfunction "2_2") (pintype "passive"))
    )
    (net (code "54") (name "/P1.11{slash}I2C_SCL") (class "Default")
      (node (ref "R109") (pin "2") (pinfunction "2_2") (pintype "passive"))
      (node (ref "R117") (pin "2") (pinfunction "2_2") (pintype "passive"))
    )
    (net (code "55") (name "/P1.12{slash}I2C_SDA") (class "Default")
      (node (ref "R111") (pin "2") (pinfunction "2_2") (pintype "passive"))
      (node (ref "R131") (pin "2") (pinfunction "2_2") (pintype "passive"))
    )
    (net (code "56") (name "/P1.13{slash}LED_RED") (class "Default")
      (node (ref "R95") (pin "2") (pinfunction "2_2") (pintype "passive"))
      (node (ref "U11") (pin "1") (pinfunction "A1_1") (pintype "input"))
    )
    (net (code "57") (name "/P1.14{slash}WAKE-HOST{slash}UART1_DTR") (class "Default")
      (node (ref "R114") (pin "2") (pinfunction "2_2") (pintype "passive"))
      (node (ref "U12") (pin "6") (pinfunction "A5_6") (pintype "input"))
    )
    (net (code "58") (name "/P2.06{slash}SPI1_CLK") (class "Default")
      (node (ref "R99") (pin "2") (pinfunction "2_2") (pintype "passive"))
      (node (ref "U11") (pin "5") (pinfunction "A4_5") (pintype "input"))
    )
    (net (code "59") (name "/P2.07{slash}SPI2_CS1{slash}SPI_DCX") (class "Default")
      (node (ref "R113") (pin "2") (pinfunction "2_2") (pintype "passive"))
    )
    (net (code "60") (name "/P2.08{slash}SPI1_MOSI") (class "Default")
      (node (ref "R102") (pin "2") (pinfunction "2_2") (pintype "passive"))
      (node (ref "U11") (pin "7") (pinfunction "A6_7") (pintype "input"))
    )
    (net (code "61") (name "/P2.09{slash}SPI1_MISO") (class "Default")
      (node (ref "R100") (pin "2") (pinfunction "2_2") (pintype "passive"))
    )
    (net (code "62") (name "/P2.10{slash}SPI1_CS0") (class "Default")
      (node (ref "R98") (pin "2") (pinfunction "2_2") (pintype "passive"))
      (node (ref "U11") (pin "4") (pinfunction "A3_4") (pintype "input"))
    )
    (net (code "63") (name "/U1-INT") (class "Default")
      (node (ref "R105") (pin "1") (pinfunction "1_1") (pintype "passive"))
      (node (ref "R106") (pin "2") (pinfunction "2_2") (pintype "passive"))
      (node (ref "U11") (pin "9") (pinfunction "A8_9") (pintype "input"))
    )
    (net (code "64") (name "/U1-MISO") (class "Default")
      (node (ref "R100") (pin "1") (pinfunction "1_1") (pintype "passive"))
      (node (ref "R101") (pin "2") (pinfunction "2_2") (pintype "passive"))
      (node (ref "U11") (pin "6") (pinfunction "A5_6") (pintype "input"))
    )
    (net (code "65") (name "/U1-PWM") (class "Default")
      (node (ref "R103") (pin "1") (pinfunction "1_1") (pintype "passive"))
      (node (ref "R104") (pin "2") (pinfunction "2_2") (pintype "passive"))
      (node (ref "U11") (pin "8") (pinfunction "A7_8") (pintype "input"))
    )
    (net (code "66") (name "/U1-SCL") (class "Default")
      (node (ref "R109") (pin "1") (pinfunction "1_1") (pintype "passive"))
      (node (ref "R110") (pin "2") (pinfunction "2_2") (pintype "passive"))
      (node (ref "U12") (pin "4") (pinfunction "A3_4") (pintype "input"))
    )
    (net (code "67") (name "/U1-SDA") (class "Default")
      (node (ref "R111") (pin "1") (pinfunction "1_1") (pintype "passive"))
      (node (ref "R112") (pin "2") (pinfunction "2_2") (pintype "passive"))
      (node (ref "U12") (pin "5") (pinfunction "A4_5") (pintype "input"))
    )
    (net (code "68") (name "/U1-nRESET") (class "Default")
      (node (ref "R94") (pin "1") (pinfunction "1_1") (pintype "passive"))
      (node (ref "R96") (pin "1") (pinfunction "1_1") (pintype "passive"))
      (node (ref "R97") (pin "2") (pinfunction "2_2") (pintype "passive"))
      (node (ref "U11") (pin "3") (pinfunction "A2_3") (pintype "input"))
    )
    (net (code "69") (name "/U2-CS") (class "Default")
      (node (ref "R117") (pin "1") (pinfunction "1_1") (pintype "passive"))
      (node (ref "R118") (pin "2") (pinfunction "2_2") (pintype "passive"))
      (node (ref "U12") (pin "8") (pinfunction "A7_8") (pintype "input"))
    )
    (net (code "70") (name "/U2-INT") (class "Default")
      (node (ref "R127") (pin "1") (pinfunction "1_1") (pintype "passive"))
      (node (ref "R128") (pin "2") (pinfunction "2_2") (pintype "passive"))
      (node (ref "U13") (pin "5") (pinfunction "A4_5") (pintype "input"))
    )
    (net (code "71") (name "/U2-MISO") (class "Default")
      (node (ref "R121") (pin "1") (pinfunction "1_1") (pintype "passive"))
      (node (ref "R122") (pin "2") (pinfunction "2_2") (pintype "passive"))
      (node (ref "U13") (pin "1") (pinfunction "A1_1") (pintype "input"))
    )
    (net (code "72") (name "/U2-MOSI") (class "Default")
      (node (ref "R123") (pin "1") (pinfunction "1_1") (pintype "passive"))
      (node (ref "R124") (pin "2") (pinfunction "2_2") (pintype "passive"))
      (node (ref "U13") (pin "3") (pinfunction "A2_3") (pintype "input"))
    )
    (net (code "73") (name "/U2-PWM") (class "Default")
      (node (ref "R125") (pin "1") (pinfunction "1_1") (pintype "passive"))
      (node (ref "R126") (pin "2") (pinfunction "2_2") (pintype "passive"))
      (node (ref "U13") (pin "4") (pinfunction "A3_4") (pintype "input"))
    )
    (net (code "74") (name "/U2-RX") (class "Default")
      (node (ref "R129") (pin "1") (pinfunction "1_1") (pintype "passive"))
      (node (ref "R130") (pin "2") (pinfunction "2_2") (pintype "passive"))
      (node (ref "U13") (pin "6") (pinfunction "A5_6") (pintype "input"))
    )
    (net (code "75") (name "/U2-SCK") (class "Default")
      (node (ref "R119") (pin "1") (pinfunction "1_1") (pintype "passive"))
      (node (ref "R120") (pin "2") (pinfunction "2_2") (pintype "passive"))
      (node (ref "U12") (pin "9") (pinfunction "A8_9") (pintype "input"))
    )
    (net (code "76") (name "/U2-SCL") (class "Default")
      (node (ref "R133") (pin "1") (pinfunction "1_1") (pintype "passive"))
      (node (ref "R134") (pin "2") (pinfunction "2_2") (pintype "passive"))
      (node (ref "U13") (pin "8") (pinfunction "A7_8") (pintype "input"))
    )
    (net (code "77") (name "/U2-SDA") (class "Default")
      (node (ref "R135") (pin "1") (pinfunction "1_1") (pintype "passive"))
      (node (ref "R136") (pin "2") (pinfunction "2_2") (pintype "passive"))
      (node (ref "U13") (pin "9") (pinfunction "A8_9") (pintype "input"))
    )
    (net (code "78") (name "/U2-TX") (class "Default")
      (node (ref "R131") (pin "1") (pinfunction "1_1") (pintype "passive"))
      (node (ref "R132") (pin "2") (pinfunction "2_2") (pintype "passive"))
      (node (ref "U13") (pin "7") (pinfunction "A6_7") (pintype "input"))
    )
    (net (code "79") (name "/U2-nRESET") (class "Default")
      (node (ref "R113") (pin "1") (pinfunction "1_1") (pintype "passive"))
      (node (ref "R115") (pin "1") (pinfunction "1_1") (pintype "passive"))
      (node (ref "R116") (pin "2") (pinfunction "2_2") (pintype "passive"))
      (node (ref "U12") (pin "7") (pinfunction "A6_7") (pintype "input"))
    )
    (net (code "80") (name "/nRESET") (class "Default")
      (node (ref "R115") (pin "2") (pinfunction "2_2") (pintype "passive"))
      (node (ref "R96") (pin "2") (pinfunction "2_2") (pintype "passive"))
    )
    (net (code "90") (name "GND") (class "Default")
      (node (ref "C42") (pin "2") (pinfunction "2_2") (pintype "passive"))
      (node (ref "C43") (pin "2") (pinfunction "2_2") (pintype "passive"))
      (node (ref "C44") (pin "2") (pinfunction "2_2") (pintype "passive"))
      (node (ref "C45") (pin "2") (pinfunction "2_2") (pintype "passive"))
      (node (ref "C46") (pin "2") (pinfunction "2_2") (pintype "passive"))
      (node (ref "C47") (pin "2") (pinfunction "2_2") (pintype "passive"))
      (node (ref "C48") (pin "2") (pinfunction "2_2") (pintype "passive"))
      (node (ref "C49") (pin "1") (pinfunction "1_1") (pintype "passive"))
      (node (ref "C50") (pin "2") (pinfunction "2_2") (pintype "passive"))
      (node (ref "C51") (pin "2") (pinfunction "2_2") (pintype "passive"))
      (node (ref "J17") (pin "8") (pintype "passive"))
      (node (ref "J18") (pin "8") (pintype "passive"))
      (node (ref "J19") (pin "8") (pintype "passive"))
      (node (ref "J20") (pin "8") (pintype "passive"))
      (node (ref "R202") (pin "2") (pinfunction "2_2") (pintype "passive"))
      (node (ref "R203") (pin "2") (pinfunction "2_2") (pintype "passive"))
      (node (ref "R204") (pin "2") (pinfunction "2_2") (pintype "passive"))
      (node (ref "U11") (pin "11") (pinfunction "GND_11") (pintype "power_in"))
      (node (ref "U12") (pin "11") (pinfunction "GND_11") (pintype "power_in"))
      (node (ref "U13") (pin "11") (pinfunction "GND_11") (pintype "power_in"))
    )
    (net (code "91") (name "Net-(U11-OE)") (class "Default")
      (node (ref "R190") (pin "1") (pinfunction "1_1") (pintype "passive"))
      (node (ref "R202") (pin "1") (pinfunction "1_1") (pintype "passive"))
      (node (ref "U11") (pin "10") (pinfunction "OE_10") (pintype "input"))
    )
    (net (code "92") (name "Net-(U12-OE)") (class "Default")
      (node (ref "R191") (pin "1") (pinfunction "1_1") (pintype "passive"))
      (node (ref "R203") (pin "1") (pinfunction "1_1") (pintype "passive"))
      (node (ref "U12") (pin "10") (pinfunction "OE_10") (pintype "input"))
    )
    (net (code "93") (name "Net-(U13-OE)") (class "Default")
      (node (ref "R192") (pin "1") (pinfunction "1_1") (pintype "passive"))
      (node (ref "R204") (pin "1") (pinfunction "1_1") (pintype "passive"))
      (node (ref "U13") (pin "10") (pinfunction "OE_10") (pintype "input"))
    )
    (net (code "94") (name "VDDIO_Periph") (class "Default")
      (node (ref "C45") (pin "1") (pinfunction "1_1") (pintype "passive"))
      (node (ref "C46") (pin "1") (pinfunction "1_1") (pintype "passive"))
      (node (ref "C47") (pin "1") (pinfunction "1_1") (pintype "passive"))
      (node (ref "R190") (pin "2") (pinfunction "2_2") (pintype "passive"))
      (node (ref "R191") (pin "2") (pinfunction "2_2") (pintype "passive"))
      (node (ref "R192") (pin "2") (pinfunction "2_2") (pintype "passive"))
      (node (ref "U11") (pin "2") (pinfunction "VCCA_2") (pintype "power_in"))
      (node (ref "U12") (pin "2") (pinfunction "VCCA_2") (pintype "power_in"))
      (node (ref "U13") (pin "2") (pinfunction "VCCA_2") (pintype "power_in"))
    )
  )
)
